# collatz_box.net
KiCad netlist of a schematic drawn in EAGLE
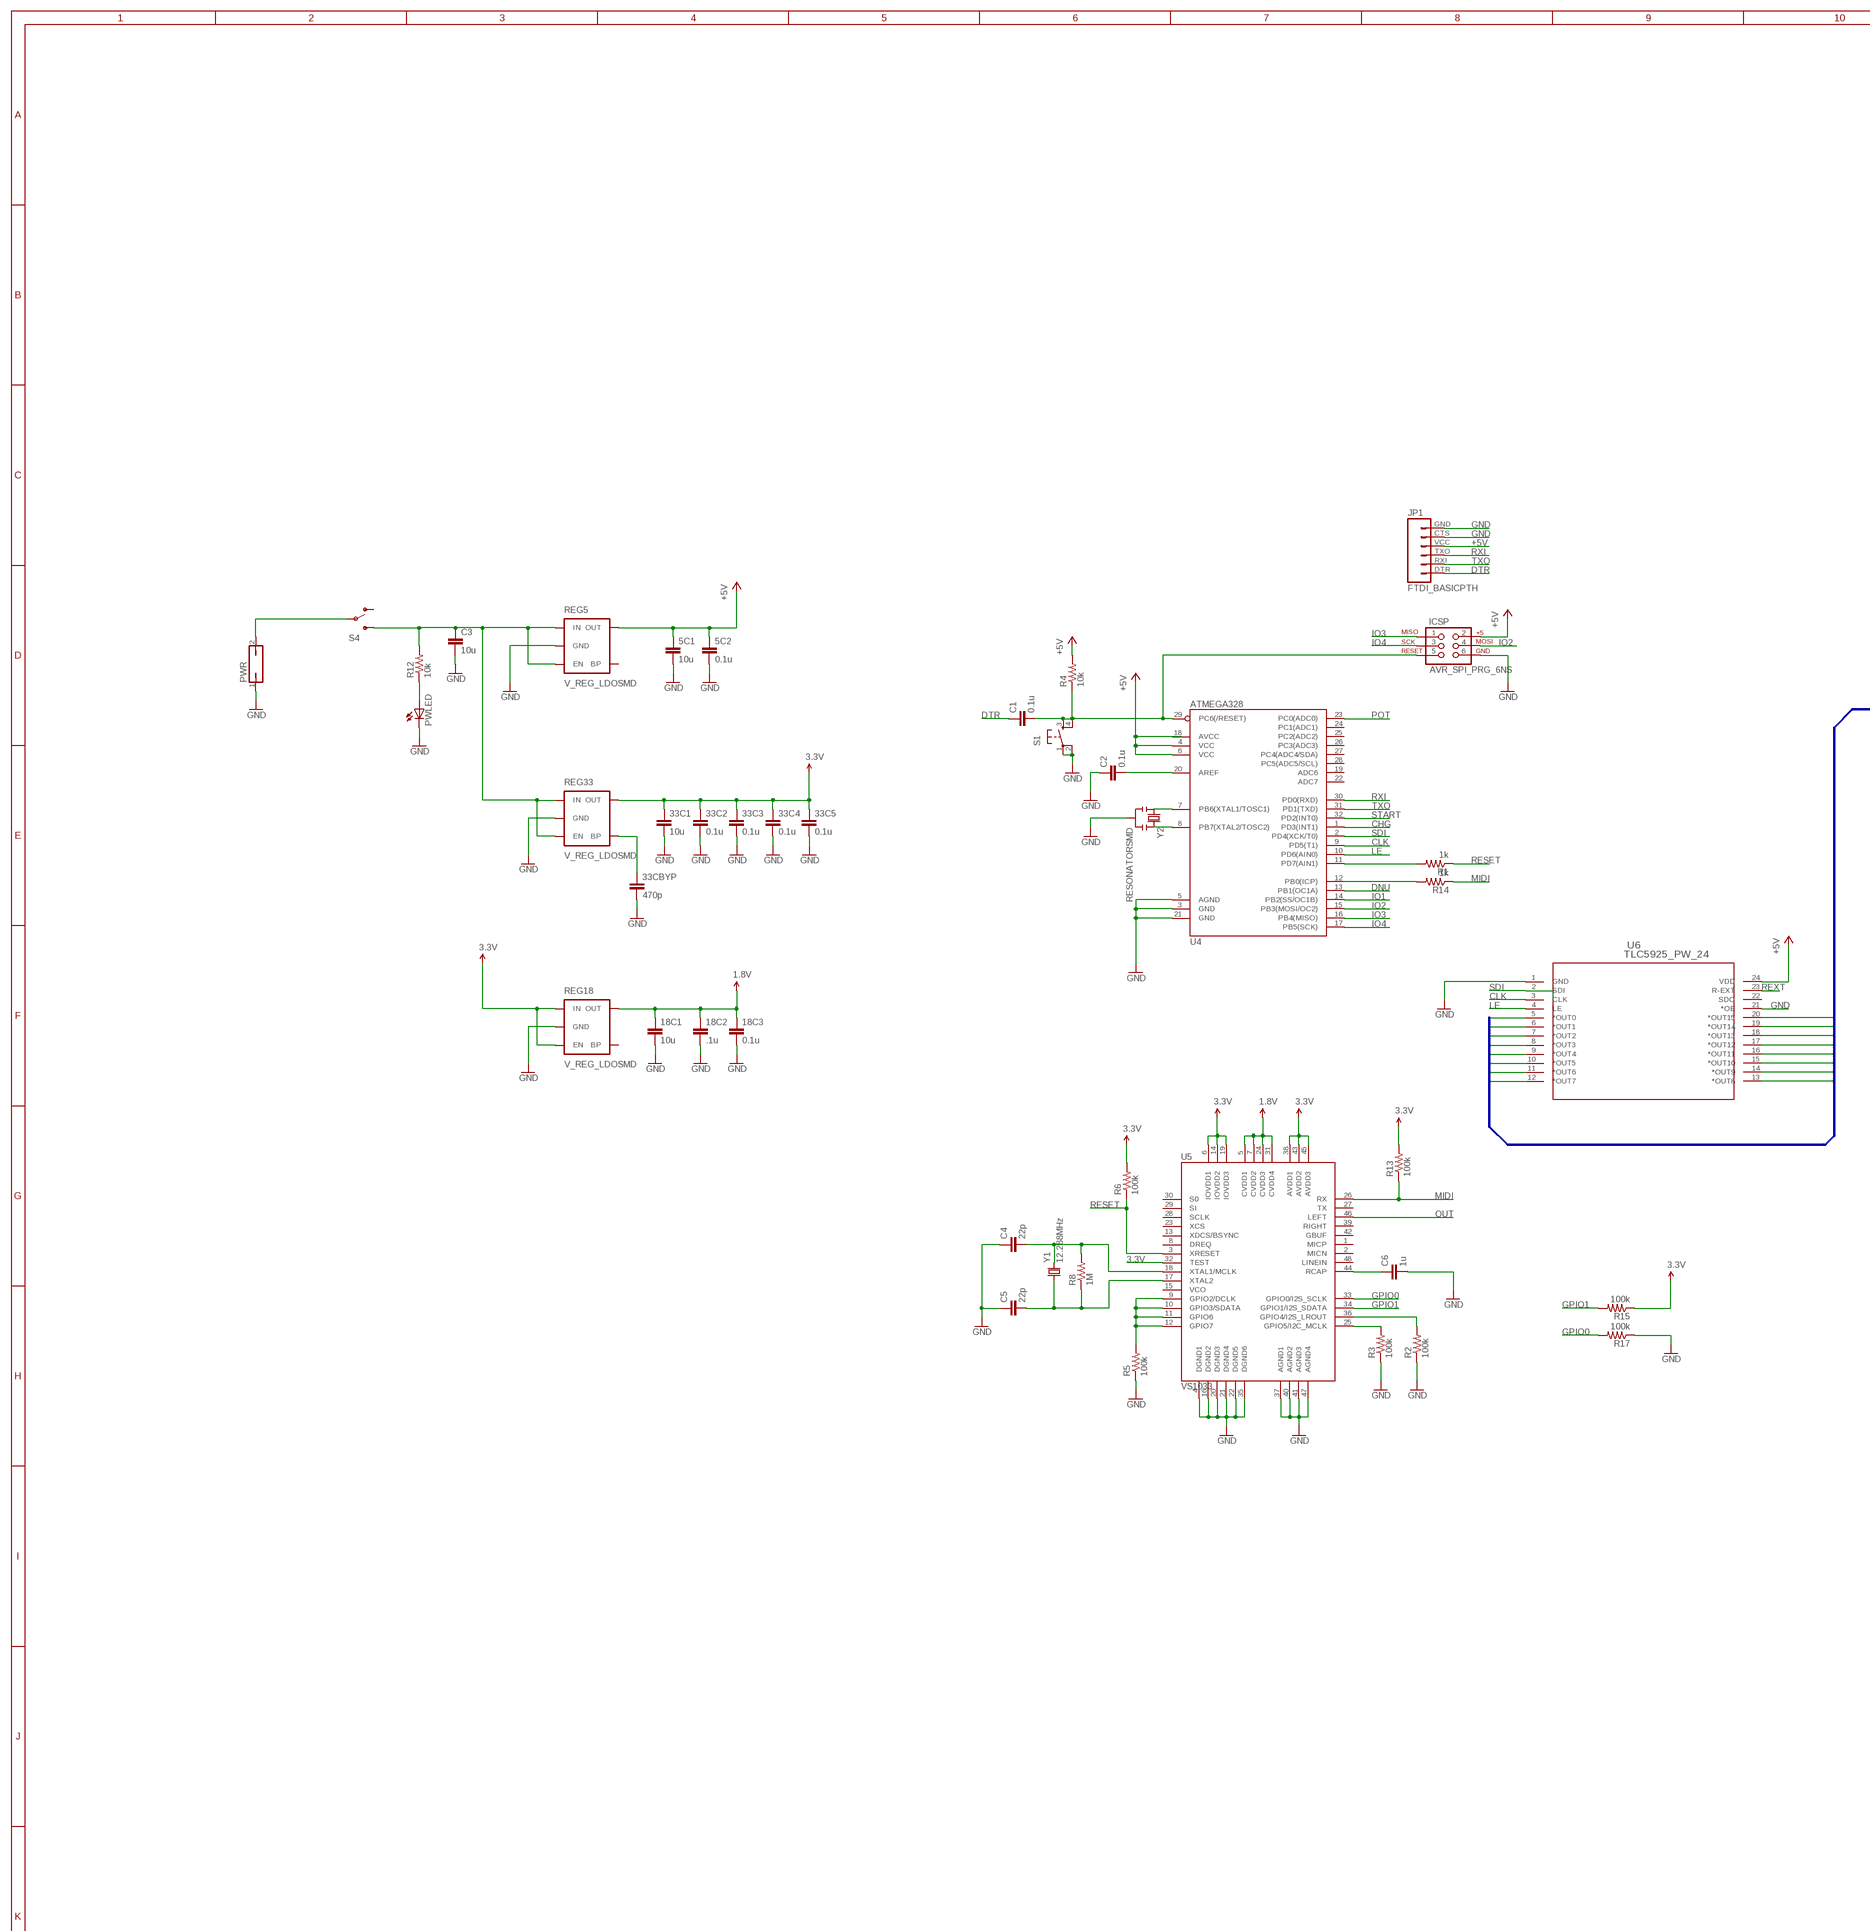
[diagram p0: schematic, sheet 1, part 1 of 3]
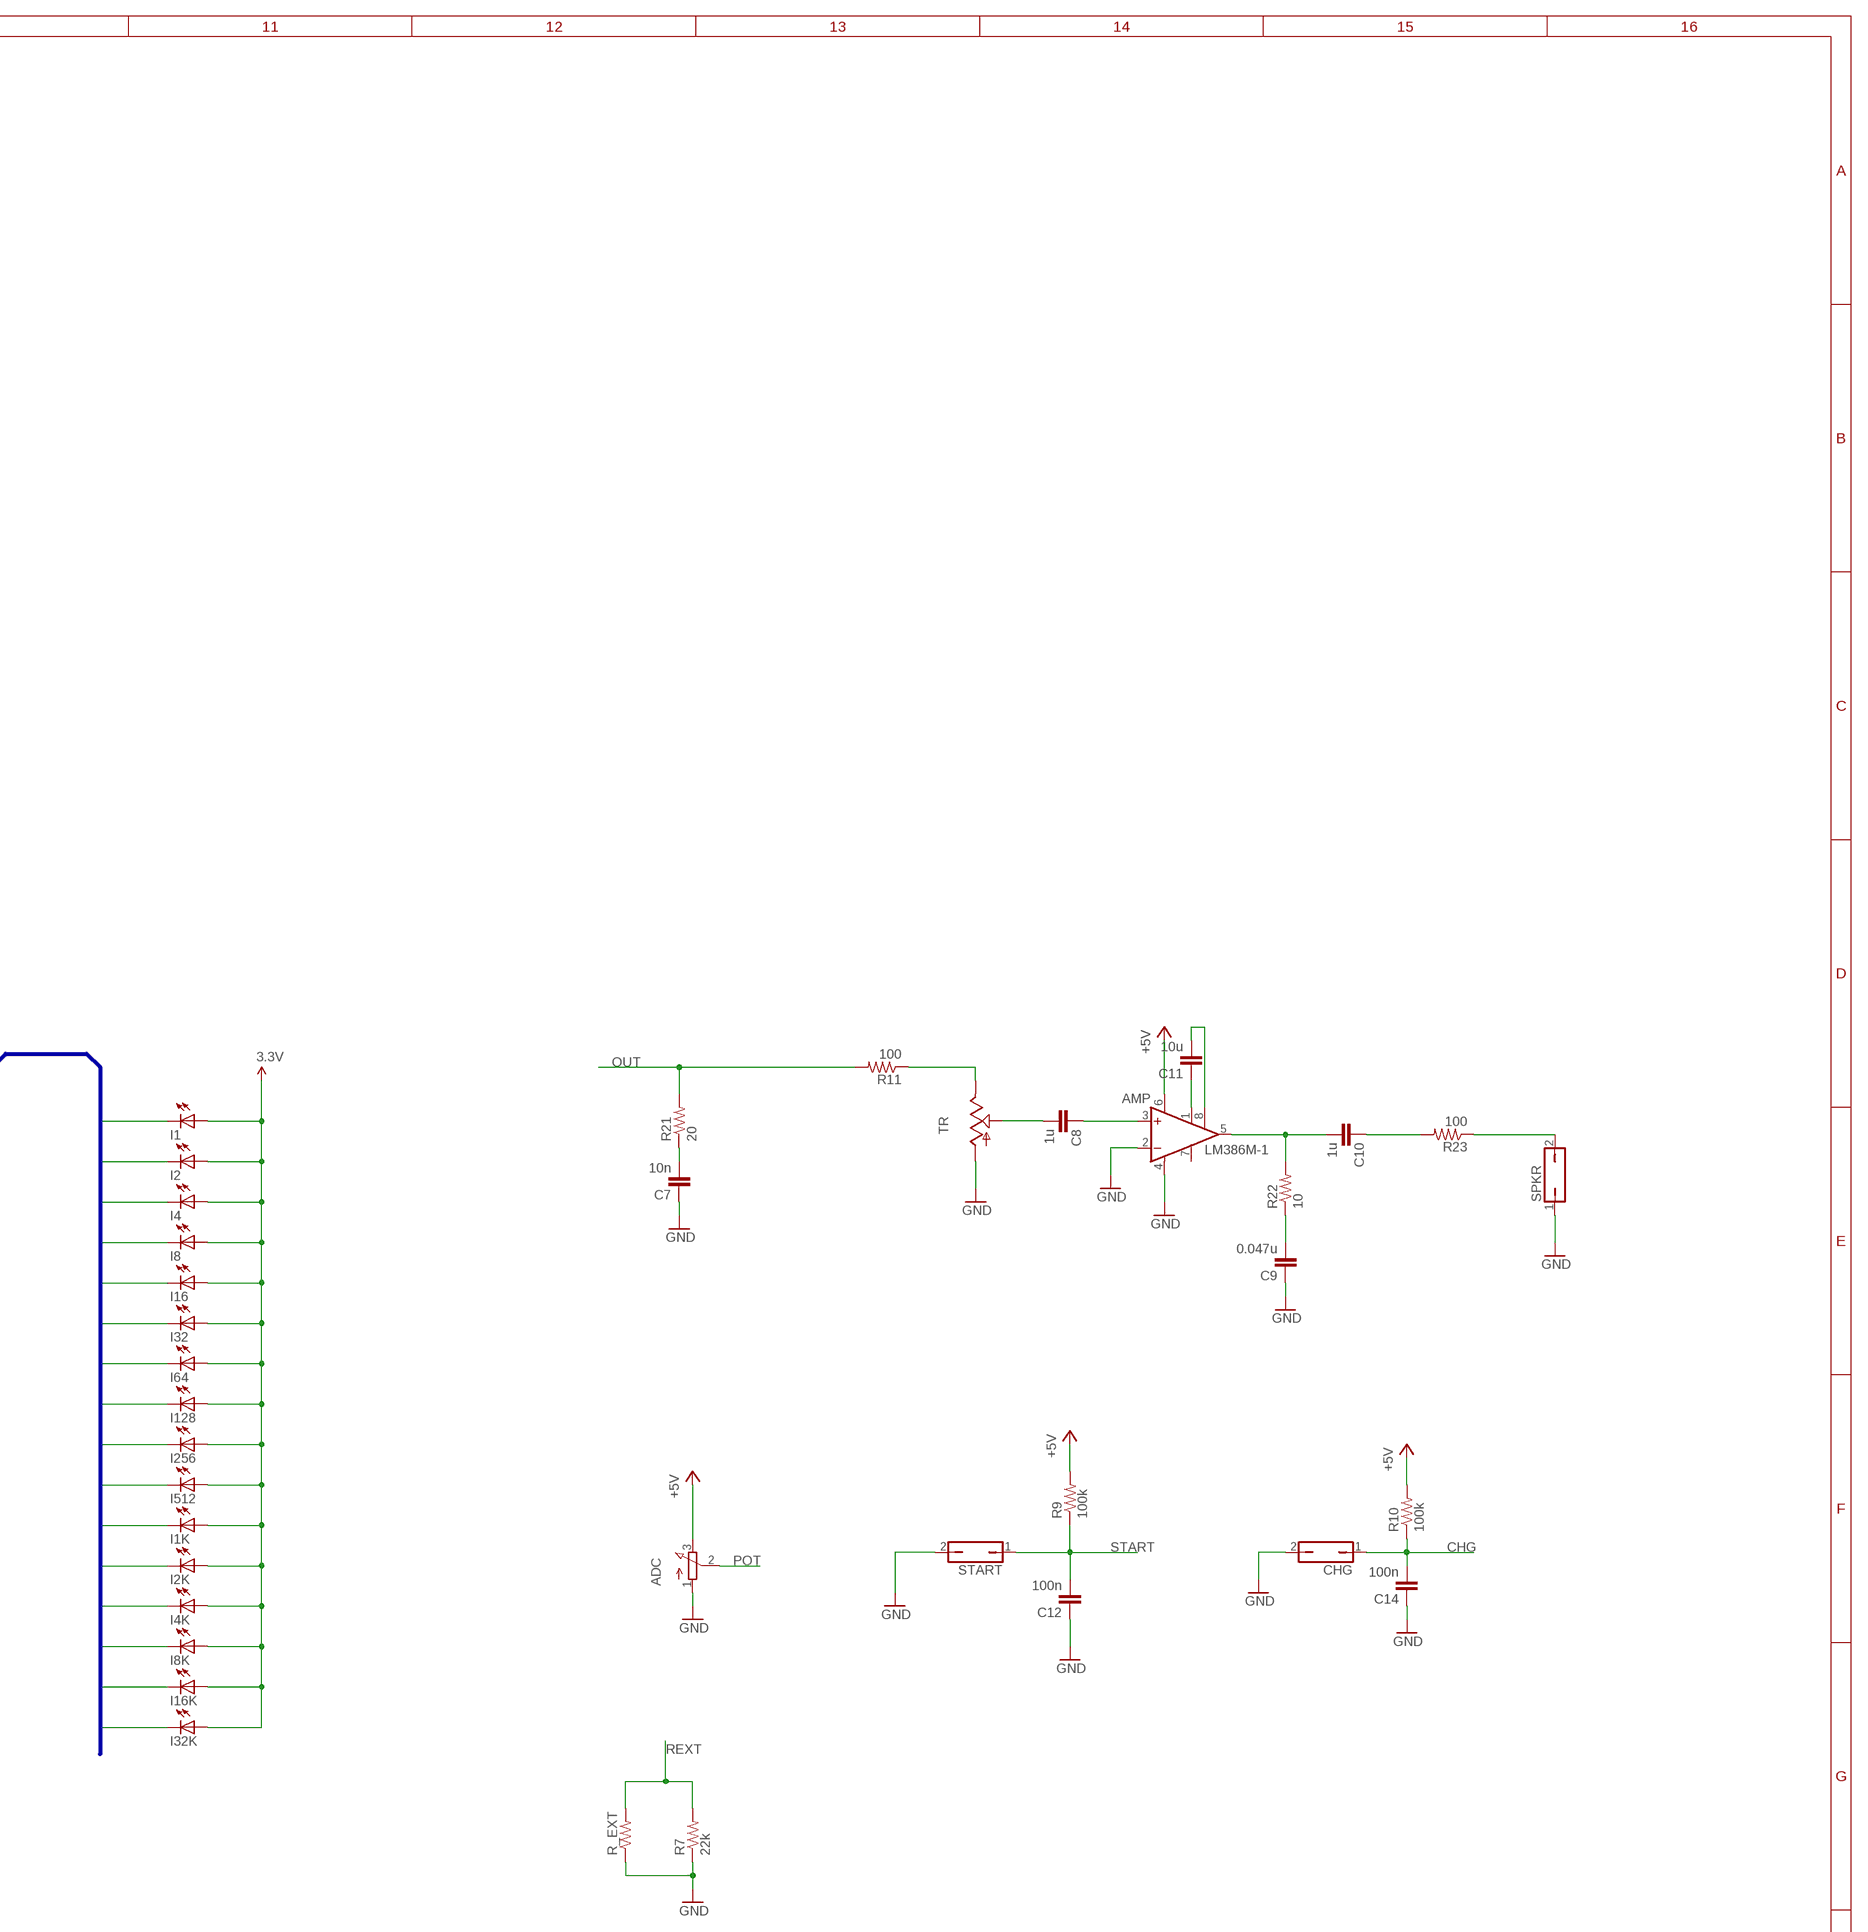
[diagram p1: schematic, sheet 1, part 2 of 3]
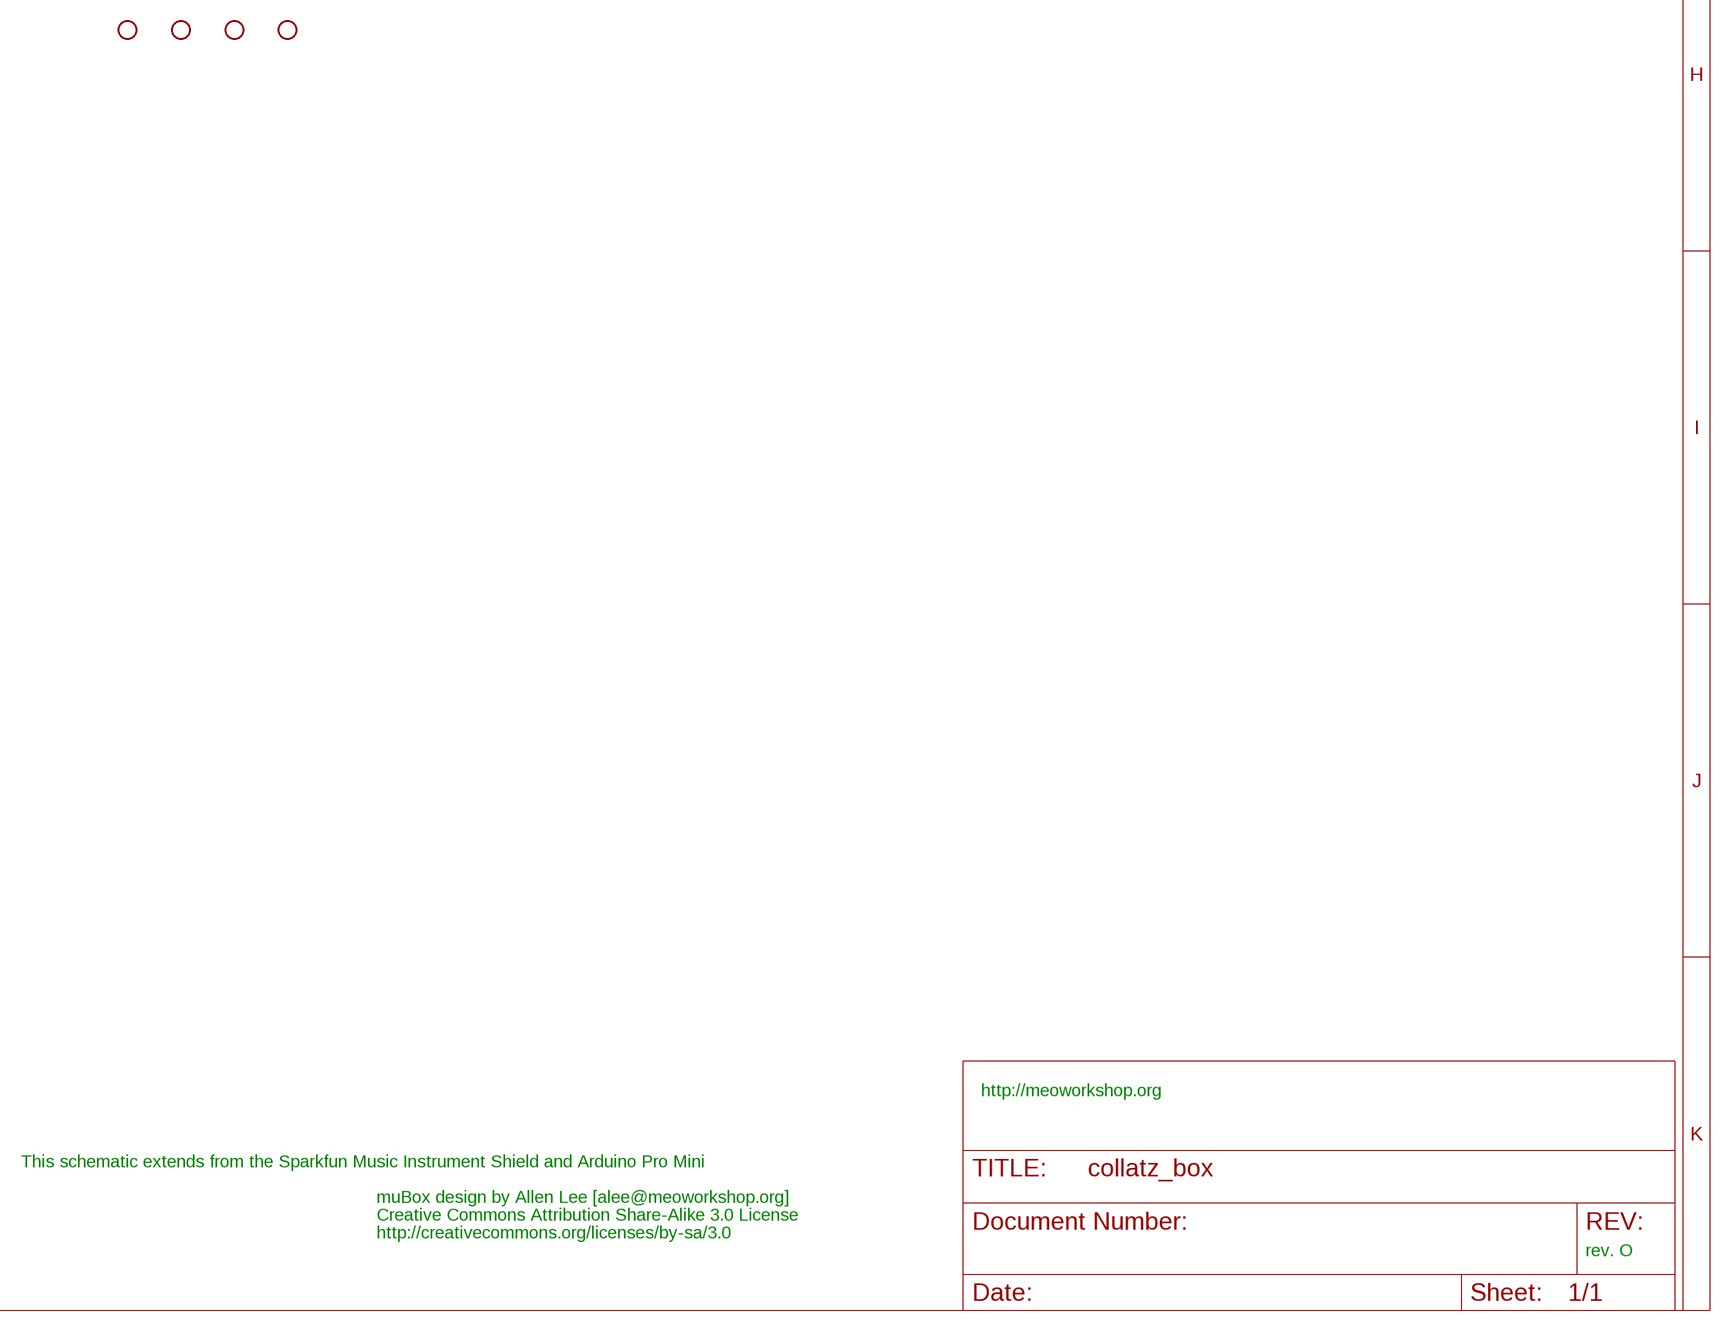
[diagram p2: schematic, sheet 1, part 3 of 3]

(export (version "E")
  (design (tool "Eeschema 10.0.6"))
  (components
    (comp (ref "5C1")
      (value "10u")
      (footprint "eagle-import:1206")
      (libsource (lib "eagle-import") (part "SparkFun-Passives_CAP1206"))
    )
    (comp (ref "5C2")
      (value "0.1u")
      (footprint "eagle-import:0805")
      (libsource (lib "eagle-import") (part "CAP0805"))
    )
    (comp (ref "18C1")
      (value "10u")
      (footprint "eagle-import:1206")
      (libsource (lib "eagle-import") (part "SparkFun-Passives_CAP1206"))
    )
    (comp (ref "18C2")
      (value ".1u")
      (footprint "eagle-import:0805")
      (libsource (lib "eagle-import") (part "CAP0805"))
    )
    (comp (ref "18C3")
      (value "0.1u")
      (footprint "eagle-import:0805")
      (libsource (lib "eagle-import") (part "CAP0805"))
    )
    (comp (ref "33C1")
      (value "10u")
      (footprint "eagle-import:1206")
      (libsource (lib "eagle-import") (part "SparkFun-Passives_CAP1206"))
    )
    (comp (ref "33C2")
      (value "0.1u")
      (footprint "eagle-import:0805")
      (libsource (lib "eagle-import") (part "CAP0805"))
    )
    (comp (ref "33C3")
      (value "0.1u")
      (footprint "eagle-import:0805")
      (libsource (lib "eagle-import") (part "CAP0805"))
    )
    (comp (ref "33C4")
      (value "0.1u")
      (footprint "eagle-import:0805")
      (libsource (lib "eagle-import") (part "CAP0805"))
    )
    (comp (ref "33C5")
      (value "0.1u")
      (footprint "eagle-import:0805")
      (libsource (lib "eagle-import") (part "CAP0805"))
    )
    (comp (ref "33CBYP")
      (value "470p")
      (footprint "eagle-import:0805")
      (libsource (lib "eagle-import") (part "CAP0805"))
    )
    (comp (ref "ADC")
      (value "3RP/1610N")
      (footprint "eagle-import:3RP_1610N")
      (libsource (lib "eagle-import") (part "3RP/1610N"))
    )
    (comp (ref "AMP")
      (value "LM386M-1")
      (footprint "eagle-import:SO08")
      (libsource (lib "eagle-import") (part "LM386?-M1"))
    )
    (comp (ref "C1")
      (value "0.1u")
      (footprint "eagle-import:0805")
      (libsource (lib "eagle-import") (part "CAP0805"))
    )
    (comp (ref "C2")
      (value "0.1u")
      (footprint "eagle-import:0805")
      (libsource (lib "eagle-import") (part "CAP0805"))
    )
    (comp (ref "C3")
      (value "10u")
      (footprint "eagle-import:1206")
      (libsource (lib "eagle-import") (part "SparkFun-Passives_CAP1206"))
    )
    (comp (ref "C4")
      (value "22p")
      (footprint "eagle-import:0805")
      (libsource (lib "eagle-import") (part "CAP0805"))
    )
    (comp (ref "C5")
      (value "22p")
      (footprint "eagle-import:0805")
      (libsource (lib "eagle-import") (part "CAP0805"))
    )
    (comp (ref "C6")
      (value "1u")
      (footprint "eagle-import:0805")
      (libsource (lib "eagle-import") (part "CAP0805"))
    )
    (comp (ref "C7")
      (value "10n")
      (footprint "eagle-import:0805")
      (libsource (lib "eagle-import") (part "CAP0805"))
    )
    (comp (ref "C8")
      (value "1u")
      (footprint "eagle-import:0805")
      (libsource (lib "eagle-import") (part "CAP0805"))
    )
    (comp (ref "C9")
      (value "0.047u")
      (footprint "eagle-import:0805")
      (libsource (lib "eagle-import") (part "CAP0805"))
    )
    (comp (ref "C10")
      (value "1u")
      (footprint "eagle-import:0805")
      (libsource (lib "eagle-import") (part "CAP0805"))
    )
    (comp (ref "C11")
      (value "10u")
      (footprint "eagle-import:0805")
      (libsource (lib "eagle-import") (part "CAP0805"))
    )
    (comp (ref "C12")
      (value "100n")
      (footprint "eagle-import:0805")
      (libsource (lib "eagle-import") (part "CAP0805"))
    )
    (comp (ref "C14")
      (value "100n")
      (footprint "eagle-import:0805")
      (libsource (lib "eagle-import") (part "CAP0805"))
    )
    (comp (ref "CHG")
      (value "JP1Q")
      (footprint "eagle-import:JP1")
      (libsource (lib "eagle-import") (part "JP1Q"))
    )
    (comp (ref "I1")
      (value "LEDCHIPLED_1206")
      (footprint "eagle-import:CHIPLED_1206")
      (libsource (lib "eagle-import") (part "LEDCHIPLED_1206"))
    )
    (comp (ref "I1K")
      (value "LEDCHIPLED_1206")
      (footprint "eagle-import:CHIPLED_1206")
      (libsource (lib "eagle-import") (part "LEDCHIPLED_1206"))
    )
    (comp (ref "I2")
      (value "LEDCHIPLED_1206")
      (footprint "eagle-import:CHIPLED_1206")
      (libsource (lib "eagle-import") (part "LEDCHIPLED_1206"))
    )
    (comp (ref "I2K")
      (value "LEDCHIPLED_1206")
      (footprint "eagle-import:CHIPLED_1206")
      (libsource (lib "eagle-import") (part "LEDCHIPLED_1206"))
    )
    (comp (ref "I4")
      (value "LEDCHIPLED_1206")
      (footprint "eagle-import:CHIPLED_1206")
      (libsource (lib "eagle-import") (part "LEDCHIPLED_1206"))
    )
    (comp (ref "I4K")
      (value "LEDCHIPLED_1206")
      (footprint "eagle-import:CHIPLED_1206")
      (libsource (lib "eagle-import") (part "LEDCHIPLED_1206"))
    )
    (comp (ref "I8")
      (value "LEDCHIPLED_1206")
      (footprint "eagle-import:CHIPLED_1206")
      (libsource (lib "eagle-import") (part "LEDCHIPLED_1206"))
    )
    (comp (ref "I8K")
      (value "LEDCHIPLED_1206")
      (footprint "eagle-import:CHIPLED_1206")
      (libsource (lib "eagle-import") (part "LEDCHIPLED_1206"))
    )
    (comp (ref "I16")
      (value "LEDCHIPLED_1206")
      (footprint "eagle-import:CHIPLED_1206")
      (libsource (lib "eagle-import") (part "LEDCHIPLED_1206"))
    )
    (comp (ref "I16K")
      (value "LEDCHIPLED_1206")
      (footprint "eagle-import:CHIPLED_1206")
      (libsource (lib "eagle-import") (part "LEDCHIPLED_1206"))
    )
    (comp (ref "I32")
      (value "LEDCHIPLED_1206")
      (footprint "eagle-import:CHIPLED_1206")
      (libsource (lib "eagle-import") (part "LEDCHIPLED_1206"))
    )
    (comp (ref "I32K")
      (value "LEDCHIPLED_1206")
      (footprint "eagle-import:CHIPLED_1206")
      (libsource (lib "eagle-import") (part "LEDCHIPLED_1206"))
    )
    (comp (ref "I64")
      (value "LEDCHIPLED_1206")
      (footprint "eagle-import:CHIPLED_1206")
      (libsource (lib "eagle-import") (part "LEDCHIPLED_1206"))
    )
    (comp (ref "I128")
      (value "LEDCHIPLED_1206")
      (footprint "eagle-import:CHIPLED_1206")
      (libsource (lib "eagle-import") (part "LEDCHIPLED_1206"))
    )
    (comp (ref "I256")
      (value "LEDCHIPLED_1206")
      (footprint "eagle-import:CHIPLED_1206")
      (libsource (lib "eagle-import") (part "LEDCHIPLED_1206"))
    )
    (comp (ref "I512")
      (value "LEDCHIPLED_1206")
      (footprint "eagle-import:CHIPLED_1206")
      (libsource (lib "eagle-import") (part "LEDCHIPLED_1206"))
    )
    (comp (ref "ICSP")
      (value "AVR_SPI_PRG_6NS")
      (footprint "eagle-import:2X3-NS")
      (libsource (lib "eagle-import") (part "AVR_SPI_PRG_6NS"))
    )
    (comp (ref "JP1")
      (value "FTDI_BASICPTH")
      (footprint "eagle-import:FTDI_BASIC")
      (libsource (lib "eagle-import") (part "FTDI_BASICPTH"))
    )
    (comp (ref "JP2")
      (value "STAND-OFF")
      (footprint "eagle-import:STAND-OFF")
      (libsource (lib "eagle-import") (part "STAND-OFF"))
    )
    (comp (ref "JP3")
      (value "STAND-OFF")
      (footprint "eagle-import:STAND-OFF")
      (libsource (lib "eagle-import") (part "STAND-OFF"))
    )
    (comp (ref "JP4")
      (value "STAND-OFF")
      (footprint "eagle-import:STAND-OFF")
      (libsource (lib "eagle-import") (part "STAND-OFF"))
    )
    (comp (ref "JP5")
      (value "STAND-OFF")
      (footprint "eagle-import:STAND-OFF")
      (libsource (lib "eagle-import") (part "STAND-OFF"))
    )
    (comp (ref "PWLED")
      (value "LEDCHIPLED_1206")
      (footprint "eagle-import:CHIPLED_1206")
      (libsource (lib "eagle-import") (part "LEDCHIPLED_1206"))
    )
    (comp (ref "PWR")
      (value "JP1Q")
      (footprint "eagle-import:JP1")
      (libsource (lib "eagle-import") (part "JP1Q"))
    )
    (comp (ref "R1")
      (value "1k")
      (footprint "eagle-import:0805")
      (libsource (lib "eagle-import") (part "RESISTOR0805-RES"))
    )
    (comp (ref "R2")
      (value "100k")
      (footprint "eagle-import:0805")
      (libsource (lib "eagle-import") (part "RESISTOR0805-RES"))
    )
    (comp (ref "R3")
      (value "100k")
      (footprint "eagle-import:0805")
      (libsource (lib "eagle-import") (part "RESISTOR0805-RES"))
    )
    (comp (ref "R4")
      (value "10k")
      (footprint "eagle-import:0805")
      (libsource (lib "eagle-import") (part "RESISTOR0805-RES"))
    )
    (comp (ref "R5")
      (value "100k")
      (footprint "eagle-import:0805")
      (libsource (lib "eagle-import") (part "RESISTOR0805-RES"))
    )
    (comp (ref "R6")
      (value "100k")
      (footprint "eagle-import:0805")
      (libsource (lib "eagle-import") (part "RESISTOR0805-RES"))
    )
    (comp (ref "R7")
      (value "22k")
      (footprint "eagle-import:0805")
      (libsource (lib "eagle-import") (part "RESISTOR0805-RES"))
    )
    (comp (ref "R8")
      (value "1M")
      (footprint "eagle-import:0805")
      (libsource (lib "eagle-import") (part "RESISTOR0805-RES"))
    )
    (comp (ref "R9")
      (value "100k")
      (footprint "eagle-import:0805")
      (libsource (lib "eagle-import") (part "RESISTOR0805-RES"))
    )
    (comp (ref "R10")
      (value "100k")
      (footprint "eagle-import:0805")
      (libsource (lib "eagle-import") (part "RESISTOR0805-RES"))
    )
    (comp (ref "R11")
      (value "100")
      (footprint "eagle-import:0805")
      (libsource (lib "eagle-import") (part "RESISTOR0805-RES"))
    )
    (comp (ref "R12")
      (value "10k")
      (footprint "eagle-import:0805")
      (libsource (lib "eagle-import") (part "RESISTOR0805-RES"))
    )
    (comp (ref "R13")
      (value "100k")
      (footprint "eagle-import:0805")
      (libsource (lib "eagle-import") (part "RESISTOR0805-RES"))
    )
    (comp (ref "R14")
      (value "1k")
      (footprint "eagle-import:0805")
      (libsource (lib "eagle-import") (part "RESISTOR0805-RES"))
    )
    (comp (ref "R15")
      (value "100k")
      (footprint "eagle-import:0805")
      (libsource (lib "eagle-import") (part "RESISTOR0805-RES"))
    )
    (comp (ref "R17")
      (value "100k")
      (footprint "eagle-import:0805")
      (libsource (lib "eagle-import") (part "RESISTOR0805-RES"))
    )
    (comp (ref "R21")
      (value "20")
      (footprint "eagle-import:0805")
      (libsource (lib "eagle-import") (part "RESISTOR0805-RES"))
    )
    (comp (ref "R22")
      (value "10")
      (footprint "eagle-import:0805")
      (libsource (lib "eagle-import") (part "RESISTOR0805-RES"))
    )
    (comp (ref "R23")
      (value "100")
      (footprint "eagle-import:0805")
      (libsource (lib "eagle-import") (part "RESISTOR0805-RES"))
    )
    (comp (ref "REG5")
      (value "V_REG_LDOSMD")
      (footprint "eagle-import:SOT23-5")
      (libsource (lib "eagle-import") (part "V_REG_LDOSMD"))
    )
    (comp (ref "REG18")
      (value "V_REG_LDOSMD")
      (footprint "eagle-import:SOT23-5")
      (libsource (lib "eagle-import") (part "V_REG_LDOSMD"))
    )
    (comp (ref "REG33")
      (value "V_REG_LDOSMD")
      (footprint "eagle-import:SOT23-5")
      (libsource (lib "eagle-import") (part "V_REG_LDOSMD"))
    )
    (comp (ref "R_EXT")
      (value "RESISTORPTH-1/4W")
      (footprint "eagle-import:AXIAL-0.4")
      (libsource (lib "eagle-import") (part "SparkFun-Resistors_RESISTORPTH-1/4W"))
    )
    (comp (ref "S1")
      (value "TAC_SWITCHSMD")
      (footprint "eagle-import:TACTILE_SWITCH_SMD")
      (libsource (lib "eagle-import") (part "TAC_SWITCHSMD"))
    )
    (comp (ref "S4")
      (value "SWITCH-SPDTPTH")
      (footprint "eagle-import:SWITCH-SPDT")
      (libsource (lib "eagle-import") (part "SWITCH-SPDTPTH"))
    )
    (comp (ref "SPKR")
      (value "JP1Q")
      (footprint "eagle-import:JP1")
      (libsource (lib "eagle-import") (part "JP1Q"))
    )
    (comp (ref "START")
      (value "JP1Q")
      (footprint "eagle-import:JP1")
      (libsource (lib "eagle-import") (part "JP1Q"))
    )
    (comp (ref "TR")
      (value "TRIM_US-3223W")
      (footprint "eagle-import:3223W")
      (libsource (lib "eagle-import") (part "TRIM_US-3223W"))
    )
    (comp (ref "U4")
      (value "ATMEGA328")
      (footprint "eagle-import:TQFP32-08")
      (libsource (lib "eagle-import") (part "ATMEGA168"))
    )
    (comp (ref "U5")
      (value "VS1033")
      (footprint "eagle-import:LQFP-48")
      (libsource (lib "eagle-import") (part "VS1033"))
    )
    (comp (ref "U6")
      (value "TLC5925_PW_24")
      (footprint "eagle-import:PW24")
      (fields
        (field (name "GENERIC_PART_NUMBER") "TLC5925")
        (field (name "MANUFACTURER") "Texas Instruments")
        (field (name "MANUFACTURER_PART_NUMBER") "tlc5925_pw_24")
      )
      (libsource (lib "eagle-import") (part "TLC5925_PW_24"))
    )
    (comp (ref "Y1")
      (value "12.288MHz")
      (footprint "eagle-import:CRYSTAL-SMD-5X3")
      (libsource (lib "eagle-import") (part "CRYSTAL5X3"))
    )
    (comp (ref "Y2")
      (value "RESONATORSMD")
      (footprint "eagle-import:RESONATOR-SMD")
      (libsource (lib "eagle-import") (part "RESONATORSMD"))
    )
  )
  (nets
    (net (code "1") (name "+5V") (class "Default")
      (node (ref "5C1") (pin "1") (pinfunction "1_1") (pintype "passive"))
      (node (ref "5C2") (pin "1") (pinfunction "1_1") (pintype "passive"))
      (node (ref "ADC") (pin "3") (pinfunction "E_3") (pintype "passive"))
      (node (ref "AMP") (pin "6") (pinfunction "VS_6") (pintype "power_in"))
      (node (ref "ICSP") (pin "2") (pinfunction "2_2") (pintype "passive"))
      (node (ref "JP1") (pin "VCC") (pinfunction "4_VCC") (pintype "passive"))
      (node (ref "R10") (pin "2") (pinfunction "2_2") (pintype "passive"))
      (node (ref "R4") (pin "2") (pinfunction "2_2") (pintype "passive"))
      (node (ref "R9") (pin "2") (pinfunction "2_2") (pintype "passive"))
      (node (ref "REG5") (pin "5") (pinfunction "OUT_5") (pintype "passive"))
      (node (ref "U4") (pin "4") (pinfunction "VCC_4") (pintype "bidirectional"))
      (node (ref "U4") (pin "6") (pinfunction "VCC_6") (pintype "bidirectional"))
      (node (ref "U6") (pin "24") (pinfunction "VDD_24") (pintype "power_in"))
    )
    (net (code "2") (name "/CHG") (class "Default")
      (node (ref "C14") (pin "2") (pinfunction "2_2") (pintype "passive"))
      (node (ref "CHG") (pin "1") (pinfunction "1_1") (pintype "passive"))
      (node (ref "R10") (pin "1") (pinfunction "1_1") (pintype "passive"))
      (node (ref "U4") (pin "1") (pinfunction "PD3(INT1)_1") (pintype "bidirectional"))
    )
    (net (code "3") (name "/CLK") (class "Default")
      (node (ref "U4") (pin "9") (pinfunction "PD5(T1)_9") (pintype "bidirectional"))
      (node (ref "U6") (pin "3") (pinfunction "CLK_3") (pintype "input"))
    )
    (net (code "4") (name "/DNU") (class "Default")
      (node (ref "U4") (pin "13") (pinfunction "PB1(OC1A)_13") (pintype "bidirectional"))
    )
    (net (code "5") (name "/DTR") (class "Default")
      (node (ref "C1") (pin "1") (pinfunction "1_1") (pintype "passive"))
      (node (ref "C1") (pin "2") (pinfunction "2_2") (pintype "passive"))
      (node (ref "ICSP") (pin "5") (pinfunction "5_5") (pintype "passive"))
      (node (ref "JP1") (pin "DTR") (pinfunction "1_DTR") (pintype "passive"))
      (node (ref "R4") (pin "1") (pinfunction "1_1") (pintype "passive"))
      (node (ref "S1") (pin "3") (pinfunction "3_3") (pintype "passive"))
      (node (ref "S1") (pin "4") (pinfunction "4_4") (pintype "passive"))
      (node (ref "U4") (pin "29") (pinfunction "PC6(/RESET)_29") (pintype "bidirectional"))
    )
    (net (code "6") (name "/GPIO0") (class "Default")
      (node (ref "R17") (pin "2") (pinfunction "2_2") (pintype "passive"))
      (node (ref "U5") (pin "33") (pinfunction "GPIO0/I2S_SCLK_33") (pintype "bidirectional"))
    )
    (net (code "7") (name "/GPIO1") (class "Default")
      (node (ref "R15") (pin "2") (pinfunction "2_2") (pintype "passive"))
      (node (ref "U5") (pin "34") (pinfunction "GPIO1/I2S_SDATA_34") (pintype "bidirectional"))
    )
    (net (code "8") (name "/IO1") (class "Default")
      (node (ref "U4") (pin "14") (pinfunction "PB2(SS/OC1B)_14") (pintype "bidirectional"))
    )
    (net (code "9") (name "/IO2") (class "Default")
      (node (ref "ICSP") (pin "4") (pinfunction "4_4") (pintype "passive"))
      (node (ref "U4") (pin "15") (pinfunction "PB3(MOSI/OC2)_15") (pintype "bidirectional"))
    )
    (net (code "10") (name "/IO3") (class "Default")
      (node (ref "ICSP") (pin "1") (pinfunction "1_1") (pintype "passive"))
      (node (ref "U4") (pin "16") (pinfunction "PB4(MISO)_16") (pintype "bidirectional"))
    )
    (net (code "11") (name "/IO4") (class "Default")
      (node (ref "ICSP") (pin "3") (pinfunction "3_3") (pintype "passive"))
      (node (ref "U4") (pin "17") (pinfunction "PB5(SCK)_17") (pintype "bidirectional"))
    )
    (net (code "12") (name "/LE") (class "Default")
      (node (ref "U4") (pin "10") (pinfunction "PD6(AIN0)_10") (pintype "bidirectional"))
      (node (ref "U6") (pin "4") (pinfunction "LE_4") (pintype "input"))
    )
    (net (code "13") (name "/MIDI") (class "Default")
      (node (ref "R13") (pin "1") (pinfunction "1_1") (pintype "passive"))
      (node (ref "R14") (pin "1") (pinfunction "1_1") (pintype "passive"))
      (node (ref "U5") (pin "26") (pinfunction "RX_26") (pintype "bidirectional"))
    )
    (net (code "14") (name "/OUT") (class "Default")
      (node (ref "R11") (pin "2") (pinfunction "2_2") (pintype "passive"))
      (node (ref "R21") (pin "2") (pinfunction "2_2") (pintype "passive"))
      (node (ref "U5") (pin "46") (pinfunction "LEFT_46") (pintype "bidirectional"))
    )
    (net (code "15") (name "/OUT0") (class "Default")
      (node (ref "I1") (pin "C") (pinfunction "C_C") (pintype "passive"))
      (node (ref "U6") (pin "5") (pinfunction "*OUT0_5") (pintype "output"))
    )
    (net (code "16") (name "/OUT1") (class "Default")
      (node (ref "I2") (pin "C") (pinfunction "C_C") (pintype "passive"))
      (node (ref "U6") (pin "6") (pinfunction "*OUT1_6") (pintype "output"))
    )
    (net (code "17") (name "/OUT2") (class "Default")
      (node (ref "I4") (pin "C") (pinfunction "C_C") (pintype "passive"))
      (node (ref "U6") (pin "7") (pinfunction "*OUT2_7") (pintype "output"))
    )
    (net (code "18") (name "/OUT3") (class "Default")
      (node (ref "I8") (pin "C") (pinfunction "C_C") (pintype "passive"))
      (node (ref "U6") (pin "8") (pinfunction "*OUT3_8") (pintype "output"))
    )
    (net (code "19") (name "/OUT4") (class "Default")
      (node (ref "I16") (pin "C") (pinfunction "C_C") (pintype "passive"))
      (node (ref "U6") (pin "9") (pinfunction "*OUT4_9") (pintype "output"))
    )
    (net (code "20") (name "/OUT5") (class "Default")
      (node (ref "I32") (pin "C") (pinfunction "C_C") (pintype "passive"))
      (node (ref "U6") (pin "10") (pinfunction "*OUT5_10") (pintype "output"))
    )
    (net (code "21") (name "/OUT6") (class "Default")
      (node (ref "I64") (pin "C") (pinfunction "C_C") (pintype "passive"))
      (node (ref "U6") (pin "11") (pinfunction "*OUT6_11") (pintype "output"))
    )
    (net (code "22") (name "/OUT7") (class "Default")
      (node (ref "I128") (pin "C") (pinfunction "C_C") (pintype "passive"))
      (node (ref "U6") (pin "12") (pinfunction "*OUT7_12") (pintype "output"))
    )
    (net (code "23") (name "/OUT8") (class "Default")
      (node (ref "I256") (pin "C") (pinfunction "C_C") (pintype "passive"))
      (node (ref "U6") (pin "13") (pinfunction "*OUT8_13") (pintype "output"))
    )
    (net (code "24") (name "/OUT9") (class "Default")
      (node (ref "I512") (pin "C") (pinfunction "C_C") (pintype "passive"))
      (node (ref "U6") (pin "14") (pinfunction "*OUT9_14") (pintype "output"))
    )
    (net (code "25") (name "/OUT10") (class "Default")
      (node (ref "I1K") (pin "C") (pinfunction "C_C") (pintype "passive"))
      (node (ref "U6") (pin "15") (pinfunction "*OUT10_15") (pintype "output"))
    )
    (net (code "26") (name "/OUT11") (class "Default")
      (node (ref "I2K") (pin "C") (pinfunction "C_C") (pintype "passive"))
      (node (ref "U6") (pin "16") (pinfunction "*OUT11_16") (pintype "output"))
    )
    (net (code "27") (name "/OUT12") (class "Default")
      (node (ref "I4K") (pin "C") (pinfunction "C_C") (pintype "passive"))
      (node (ref "U6") (pin "17") (pinfunction "*OUT12_17") (pintype "output"))
    )
    (net (code "28") (name "/OUT13") (class "Default")
      (node (ref "I8K") (pin "C") (pinfunction "C_C") (pintype "passive"))
      (node (ref "U6") (pin "18") (pinfunction "*OUT13_18") (pintype "output"))
    )
    (net (code "29") (name "/OUT14") (class "Default")
      (node (ref "I16K") (pin "C") (pinfunction "C_C") (pintype "passive"))
      (node (ref "U6") (pin "19") (pinfunction "*OUT14_19") (pintype "output"))
    )
    (net (code "30") (name "/OUT15") (class "Default")
      (node (ref "I32K") (pin "C") (pinfunction "C_C") (pintype "passive"))
      (node (ref "U6") (pin "20") (pinfunction "*OUT15_20") (pintype "output"))
    )
    (net (code "31") (name "/POT") (class "Default")
      (node (ref "ADC") (pin "2") (pinfunction "S_2") (pintype "passive"))
      (node (ref "U4") (pin "23") (pinfunction "PC0(ADC0)_23") (pintype "bidirectional"))
    )
    (net (code "32") (name "/RESET") (class "Default")
      (node (ref "R1") (pin "1") (pinfunction "1_1") (pintype "passive"))
      (node (ref "R6") (pin "1") (pinfunction "1_1") (pintype "passive"))
      (node (ref "U5") (pin "3") (pinfunction "XRESET_3") (pintype "bidirectional"))
    )
    (net (code "33") (name "/REXT") (class "Default")
      (node (ref "R7") (pin "2") (pinfunction "2_2") (pintype "passive"))
      (node (ref "R_EXT") (pin "P$2") (pinfunction "2_P$2") (pintype "passive"))
      (node (ref "U6") (pin "23") (pinfunction "R-EXT_23") (pintype "input"))
    )
    (net (code "34") (name "/RXI") (class "Default")
      (node (ref "JP1") (pin "TXO") (pinfunction "3_TXO") (pintype "passive"))
      (node (ref "U4") (pin "30") (pinfunction "PD0(RXD)_30") (pintype "bidirectional"))
    )
    (net (code "35") (name "/SDI") (class "Default")
      (node (ref "U4") (pin "2") (pinfunction "PD4(XCK/T0)_2") (pintype "bidirectional"))
      (node (ref "U6") (pin "2") (pinfunction "SDI_2") (pintype "input"))
    )
    (net (code "36") (name "/START") (class "Default")
      (node (ref "C12") (pin "2") (pinfunction "2_2") (pintype "passive"))
      (node (ref "R9") (pin "1") (pinfunction "1_1") (pintype "passive"))
      (node (ref "START") (pin "1") (pinfunction "1_1") (pintype "passive"))
      (node (ref "U4") (pin "32") (pinfunction "PD2(INT0)_32") (pintype "bidirectional"))
    )
    (net (code "37") (name "/TXO") (class "Default")
      (node (ref "JP1") (pin "RXI") (pinfunction "2_RXI") (pintype "passive"))
      (node (ref "U4") (pin "31") (pinfunction "PD1(TXD)_31") (pintype "bidirectional"))
    )
    (net (code "38") (name "1.8V") (class "Default")
      (node (ref "18C1") (pin "1") (pinfunction "1_1") (pintype "passive"))
      (node (ref "18C2") (pin "1") (pinfunction "1_1") (pintype "passive"))
      (node (ref "18C3") (pin "1") (pinfunction "1_1") (pintype "passive"))
      (node (ref "REG18") (pin "5") (pinfunction "OUT_5") (pintype "passive"))
      (node (ref "U5") (pin "24") (pinfunction "CVDD3_24") (pintype "bidirectional"))
      (node (ref "U5") (pin "31") (pinfunction "CVDD4_31") (pintype "bidirectional"))
      (node (ref "U5") (pin "5") (pinfunction "CVDD1_5") (pintype "bidirectional"))
      (node (ref "U5") (pin "7") (pinfunction "CVDD2_7") (pintype "bidirectional"))
    )
    (net (code "39") (name "3.3V") (class "Default")
      (node (ref "33C1") (pin "1") (pinfunction "1_1") (pintype "passive"))
      (node (ref "33C2") (pin "1") (pinfunction "1_1") (pintype "passive"))
      (node (ref "33C3") (pin "1") (pinfunction "1_1") (pintype "passive"))
      (node (ref "33C4") (pin "1") (pinfunction "1_1") (pintype "passive"))
      (node (ref "33C5") (pin "1") (pinfunction "1_1") (pintype "passive"))
      (node (ref "I1") (pin "A") (pinfunction "A_A") (pintype "passive"))
      (node (ref "I128") (pin "A") (pinfunction "A_A") (pintype "passive"))
      (node (ref "I16") (pin "A") (pinfunction "A_A") (pintype "passive"))
      (node (ref "I16K") (pin "A") (pinfunction "A_A") (pintype "passive"))
      (node (ref "I1K") (pin "A") (pinfunction "A_A") (pintype "passive"))
      (node (ref "I2") (pin "A") (pinfunction "A_A") (pintype "passive"))
      (node (ref "I256") (pin "A") (pinfunction "A_A") (pintype "passive"))
      (node (ref "I2K") (pin "A") (pinfunction "A_A") (pintype "passive"))
      (node (ref "I32") (pin "A") (pinfunction "A_A") (pintype "passive"))
      (node (ref "I32K") (pin "A") (pinfunction "A_A") (pintype "passive"))
      (node (ref "I4") (pin "A") (pinfunction "A_A") (pintype "passive"))
      (node (ref "I4K") (pin "A") (pinfunction "A_A") (pintype "passive"))
      (node (ref "I512") (pin "A") (pinfunction "A_A") (pintype "passive"))
      (node (ref "I64") (pin "A") (pinfunction "A_A") (pintype "passive"))
      (node (ref "I8") (pin "A") (pinfunction "A_A") (pintype "passive"))
      (node (ref "I8K") (pin "A") (pinfunction "A_A") (pintype "passive"))
      (node (ref "R13") (pin "2") (pinfunction "2_2") (pintype "passive"))
      (node (ref "R15") (pin "1") (pinfunction "1_1") (pintype "passive"))
      (node (ref "R6") (pin "2") (pinfunction "2_2") (pintype "passive"))
      (node (ref "REG18") (pin "1") (pinfunction "IN_1") (pintype "input"))
      (node (ref "REG18") (pin "3") (pinfunction "EN_3") (pintype "input"))
      (node (ref "REG33") (pin "5") (pinfunction "OUT_5") (pintype "passive"))
      (node (ref "U5") (pin "14") (pinfunction "IOVDD2_14") (pintype "bidirectional"))
      (node (ref "U5") (pin "19") (pinfunction "IOVDD3_19") (pintype "bidirectional"))
      (node (ref "U5") (pin "32") (pinfunction "TEST_32") (pintype "bidirectional"))
      (node (ref "U5") (pin "38") (pinfunction "AVDD1_38") (pintype "bidirectional"))
      (node (ref "U5") (pin "43") (pinfunction "AVDD2_43") (pintype "bidirectional"))
      (node (ref "U5") (pin "45") (pinfunction "AVDD3_45") (pintype "bidirectional"))
      (node (ref "U5") (pin "6") (pinfunction "IOVDD1_6") (pintype "bidirectional"))
    )
    (net (code "40") (name "GND") (class "Default")
      (node (ref "18C1") (pin "2") (pinfunction "2_2") (pintype "passive"))
      (node (ref "18C2") (pin "2") (pinfunction "2_2") (pintype "passive"))
      (node (ref "18C3") (pin "2") (pinfunction "2_2") (pintype "passive"))
      (node (ref "33C1") (pin "2") (pinfunction "2_2") (pintype "passive"))
      (node (ref "33C2") (pin "2") (pinfunction "2_2") (pintype "passive"))
      (node (ref "33C3") (pin "2") (pinfunction "2_2") (pintype "passive"))
      (node (ref "33C4") (pin "2") (pinfunction "2_2") (pintype "passive"))
      (node (ref "33C5") (pin "2") (pinfunction "2_2") (pintype "passive"))
      (node (ref "33CBYP") (pin "2") (pinfunction "2_2") (pintype "passive"))
      (node (ref "5C1") (pin "2") (pinfunction "2_2") (pintype "passive"))
      (node (ref "5C2") (pin "2") (pinfunction "2_2") (pintype "passive"))
      (node (ref "ADC") (pin "1") (pinfunction "A_1") (pintype "passive"))
      (node (ref "AMP") (pin "2") (pinfunction "-IN_2") (pintype "input"))
      (node (ref "AMP") (pin "4") (pinfunction "GND_4") (pintype "power_in"))
      (node (ref "C12") (pin "1") (pinfunction "1_1") (pintype "passive"))
      (node (ref "C14") (pin "1") (pinfunction "1_1") (pintype "passive"))
      (node (ref "C2") (pin "1") (pinfunction "1_1") (pintype "passive"))
      (node (ref "C3") (pin "2") (pinfunction "2_2") (pintype "passive"))
      (node (ref "C4") (pin "1") (pinfunction "1_1") (pintype "passive"))
      (node (ref "C5") (pin "1") (pinfunction "1_1") (pintype "passive"))
      (node (ref "C6") (pin "2") (pinfunction "2_2") (pintype "passive"))
      (node (ref "C7") (pin "1") (pinfunction "1_1") (pintype "passive"))
      (node (ref "C9") (pin "1") (pinfunction "1_1") (pintype "passive"))
      (node (ref "CHG") (pin "2") (pinfunction "2_2") (pintype "passive"))
      (node (ref "ICSP") (pin "6") (pinfunction "6_6") (pintype "passive"))
      (node (ref "JP1") (pin "CTS") (pinfunction "5_CTS") (pintype "passive"))
      (node (ref "JP1") (pin "GND") (pinfunction "6_GND") (pintype "passive"))
      (node (ref "PWLED") (pin "C") (pinfunction "C_C") (pintype "passive"))
      (node (ref "PWR") (pin "1") (pinfunction "1_1") (pintype "passive"))
      (node (ref "R17") (pin "1") (pinfunction "1_1") (pintype "passive"))
      (node (ref "R2") (pin "1") (pinfunction "1_1") (pintype "passive"))
      (node (ref "R3") (pin "1") (pinfunction "1_1") (pintype "passive"))
      (node (ref "R5") (pin "1") (pinfunction "1_1") (pintype "passive"))
      (node (ref "R7") (pin "1") (pinfunction "1_1") (pintype "passive"))
      (node (ref "REG18") (pin "2") (pinfunction "GND_2") (pintype "input"))
      (node (ref "REG33") (pin "2") (pinfunction "GND_2") (pintype "input"))
      (node (ref "REG5") (pin "2") (pinfunction "GND_2") (pintype "input"))
      (node (ref "R_EXT") (pin "P$1") (pinfunction "1_P$1") (pintype "passive"))
      (node (ref "S1") (pin "1") (pinfunction "1_1") (pintype "passive"))
      (node (ref "S1") (pin "2") (pinfunction "2_2") (pintype "passive"))
      (node (ref "SPKR") (pin "1") (pinfunction "1_1") (pintype "passive"))
      (node (ref "START") (pin "2") (pinfunction "2_2") (pintype "passive"))
      (node (ref "TR") (pin "1") (pinfunction "A_1") (pintype "passive"))
      (node (ref "U4") (pin "21") (pinfunction "GND_21") (pintype "bidirectional"))
      (node (ref "U4") (pin "3") (pinfunction "GND_3") (pintype "bidirectional"))
      (node (ref "U4") (pin "5") (pinfunction "AGND_5") (pintype "bidirectional"))
      (node (ref "U5") (pin "16") (pinfunction "DGND2_16") (pintype "bidirectional"))
      (node (ref "U5") (pin "20") (pinfunction "DGND3_20") (pintype "bidirectional"))
      (node (ref "U5") (pin "21") (pinfunction "DGND4_21") (pintype "bidirectional"))
      (node (ref "U5") (pin "22") (pinfunction "DGND5_22") (pintype "bidirectional"))
      (node (ref "U5") (pin "35") (pinfunction "DGND6_35") (pintype "bidirectional"))
      (node (ref "U5") (pin "37") (pinfunction "AGND1_37") (pintype "bidirectional"))
      (node (ref "U5") (pin "4") (pinfunction "DGND1_4") (pintype "bidirectional"))
      (node (ref "U5") (pin "40") (pinfunction "AGND2_40") (pintype "bidirectional"))
      (node (ref "U5") (pin "41") (pinfunction "AGND3_41") (pintype "bidirectional"))
      (node (ref "U5") (pin "47") (pinfunction "AGND4_47") (pintype "bidirectional"))
      (node (ref "U6") (pin "1") (pinfunction "GND_1") (pintype "power_in"))
      (node (ref "U6") (pin "21") (pinfunction "*OE_21") (pintype "output"))
      (node (ref "Y2") (pin "2") (pinfunction "2_2") (pintype "passive"))
    )
    (net (code "41") (name "Net-(AMP-+IN)") (class "Default")
      (node (ref "AMP") (pin "3") (pinfunction "+IN_3") (pintype "input"))
      (node (ref "C8") (pin "1") (pinfunction "1_1") (pintype "passive"))
    )
    (net (code "42") (name "Net-(AMP-GAIN-Pad1)") (class "Default")
      (node (ref "AMP") (pin "1") (pinfunction "GAIN_1") (pintype "passive"))
      (node (ref "C11") (pin "1") (pinfunction "1_1") (pintype "passive"))
    )
    (net (code "43") (name "Net-(AMP-GAIN-Pad8)") (class "Default")
      (node (ref "AMP") (pin "8") (pinfunction "GAIN_8") (pintype "passive"))
      (node (ref "C11") (pin "2") (pinfunction "2_2") (pintype "passive"))
    )
    (net (code "44") (name "Net-(AMP-OUT)") (class "Default")
      (node (ref "AMP") (pin "5") (pinfunction "OUT_5") (pintype "output"))
      (node (ref "C10") (pin "2") (pinfunction "2_2") (pintype "passive"))
      (node (ref "R22") (pin "2") (pinfunction "2_2") (pintype "passive"))
    )
    (net (code "45") (name "Net-(C7-Pad2)") (class "Default")
      (node (ref "C7") (pin "2") (pinfunction "2_2") (pintype "passive"))
      (node (ref "R21") (pin "1") (pinfunction "1_1") (pintype "passive"))
    )
    (net (code "46") (name "Net-(C9-Pad2)") (class "Default")
      (node (ref "C9") (pin "2") (pinfunction "2_2") (pintype "passive"))
      (node (ref "R22") (pin "1") (pinfunction "1_1") (pintype "passive"))
    )
    (net (code "47") (name "Net-(C10-Pad1)") (class "Default")
      (node (ref "C10") (pin "1") (pinfunction "1_1") (pintype "passive"))
      (node (ref "R23") (pin "2") (pinfunction "2_2") (pintype "passive"))
    )
    (net (code "48") (name "Net-(PWLED-PadA)") (class "Default")
      (node (ref "PWLED") (pin "A") (pinfunction "A_A") (pintype "passive"))
      (node (ref "R12") (pin "1") (pinfunction "1_1") (pintype "passive"))
    )
    (net (code "49") (name "Net-(R23-Pad1)") (class "Default")
      (node (ref "R23") (pin "1") (pinfunction "1_1") (pintype "passive"))
      (node (ref "SPKR") (pin "2") (pinfunction "2_2") (pintype "passive"))
    )
    (net (code "50") (name "Net-(REG33-BP)") (class "Default")
      (node (ref "33CBYP") (pin "1") (pinfunction "1_1") (pintype "passive"))
      (node (ref "REG33") (pin "4") (pinfunction "BP_4") (pintype "input"))
    )
    (net (code "51") (name "Net-(REG33-EN)") (class "Default")
      (node (ref "C3") (pin "1") (pinfunction "1_1") (pintype "passive"))
      (node (ref "R12") (pin "2") (pinfunction "2_2") (pintype "passive"))
      (node (ref "REG33") (pin "1") (pinfunction "IN_1") (pintype "input"))
      (node (ref "REG33") (pin "3") (pinfunction "EN_3") (pintype "input"))
      (node (ref "REG5") (pin "1") (pinfunction "IN_1") (pintype "input"))
      (node (ref "REG5") (pin "3") (pinfunction "EN_3") (pintype "input"))
      (node (ref "S4") (pin "3") (pinfunction "S_3") (pintype "passive"))
    )
    (net (code "52") (name "Net-(S4-P)") (class "Default")
      (node (ref "PWR") (pin "2") (pinfunction "2_2") (pintype "passive"))
      (node (ref "S4") (pin "2") (pinfunction "P_2") (pintype "passive"))
    )
    (net (code "53") (name "Net-(TR-E)") (class "Default")
      (node (ref "R11") (pin "1") (pinfunction "1_1") (pintype "passive"))
      (node (ref "TR") (pin "3") (pinfunction "E_3") (pintype "passive"))
    )
    (net (code "54") (name "Net-(TR-S)") (class "Default")
      (node (ref "C8") (pin "2") (pinfunction "2_2") (pintype "passive"))
      (node (ref "TR") (pin "2") (pinfunction "S_2") (pintype "passive"))
    )
    (net (code "55") (name "Net-(U4-AREF)") (class "Default")
      (node (ref "C2") (pin "2") (pinfunction "2_2") (pintype "passive"))
      (node (ref "U4") (pin "20") (pinfunction "AREF_20") (pintype "bidirectional"))
    )
    (net (code "56") (name "Net-(U4-PB0(ICP))") (class "Default")
      (node (ref "R14") (pin "2") (pinfunction "2_2") (pintype "passive"))
      (node (ref "U4") (pin "12") (pinfunction "PB0(ICP)_12") (pintype "bidirectional"))
    )
    (net (code "57") (name "Net-(U4-PB6(XTAL1{slash}TOSC1))") (class "Default")
      (node (ref "U4") (pin "7") (pinfunction "PB6(XTAL1/TOSC1)_7") (pintype "bidirectional"))
      (node (ref "Y2") (pin "1") (pinfunction "1_1") (pintype "passive"))
    )
    (net (code "58") (name "Net-(U4-PB7(XTAL2{slash}TOSC2))") (class "Default")
      (node (ref "U4") (pin "8") (pinfunction "PB7(XTAL2/TOSC2)_8") (pintype "bidirectional"))
      (node (ref "Y2") (pin "3") (pinfunction "3_3") (pintype "passive"))
    )
    (net (code "59") (name "Net-(U4-PD7(AIN1))") (class "Default")
      (node (ref "R1") (pin "2") (pinfunction "2_2") (pintype "passive"))
      (node (ref "U4") (pin "11") (pinfunction "PD7(AIN1)_11") (pintype "bidirectional"))
    )
    (net (code "60") (name "Net-(U5-GPIO2{slash}DCLK)") (class "Default")
      (node (ref "R5") (pin "2") (pinfunction "2_2") (pintype "passive"))
      (node (ref "U5") (pin "10") (pinfunction "GPIO3/SDATA_10") (pintype "bidirectional"))
      (node (ref "U5") (pin "11") (pinfunction "GPIO6_11") (pintype "bidirectional"))
      (node (ref "U5") (pin "12") (pinfunction "GPIO7_12") (pintype "bidirectional"))
      (node (ref "U5") (pin "9") (pinfunction "GPIO2/DCLK_9") (pintype "bidirectional"))
    )
    (net (code "61") (name "Net-(U5-GPIO4{slash}I2S_LROUT)") (class "Default")
      (node (ref "R2") (pin "2") (pinfunction "2_2") (pintype "passive"))
      (node (ref "U5") (pin "36") (pinfunction "GPIO4/I2S_LROUT_36") (pintype "bidirectional"))
    )
    (net (code "62") (name "Net-(U5-GPIO5{slash}I2C_MCLK)") (class "Default")
      (node (ref "R3") (pin "2") (pinfunction "2_2") (pintype "passive"))
      (node (ref "U5") (pin "25") (pinfunction "GPIO5/I2C_MCLK_25") (pintype "bidirectional"))
    )
    (net (code "63") (name "Net-(U5-RCAP)") (class "Default")
      (node (ref "C6") (pin "1") (pinfunction "1_1") (pintype "passive"))
      (node (ref "U5") (pin "44") (pinfunction "RCAP_44") (pintype "bidirectional"))
    )
    (net (code "64") (name "Net-(U5-XTAL1{slash}MCLK)") (class "Default")
      (node (ref "C4") (pin "2") (pinfunction "2_2") (pintype "passive"))
      (node (ref "R8") (pin "2") (pinfunction "2_2") (pintype "passive"))
      (node (ref "U5") (pin "18") (pinfunction "XTAL1/MCLK_18") (pintype "bidirectional"))
      (node (ref "Y1") (pin "3") (pinfunction "2_3") (pintype "passive"))
    )
    (net (code "65") (name "Net-(U5-XTAL2)") (class "Default")
      (node (ref "C5") (pin "2") (pinfunction "2_2") (pintype "passive"))
      (node (ref "R8") (pin "1") (pinfunction "1_1") (pintype "passive"))
      (node (ref "U5") (pin "17") (pinfunction "XTAL2_17") (pintype "bidirectional"))
      (node (ref "Y1") (pin "1") (pinfunction "1_1") (pintype "passive"))
    )
    (net (code "66") (name "unconnected-(AMP-BYPASS-Pad7)") (class "Default")
      (node (ref "AMP") (pin "7") (pinfunction "BYPASS_7") (pintype "passive"))
    )
    (net (code "67") (name "unconnected-(REG5-BP-Pad4)") (class "Default")
      (node (ref "REG5") (pin "4") (pinfunction "BP_4") (pintype "input"))
    )
    (net (code "68") (name "unconnected-(REG18-BP-Pad4)") (class "Default")
      (node (ref "REG18") (pin "4") (pinfunction "BP_4") (pintype "input"))
    )
    (net (code "69") (name "unconnected-(S4-O-Pad1)") (class "Default")
      (node (ref "S4") (pin "1") (pinfunction "O_1") (pintype "passive"))
    )
    (net (code "70") (name "unconnected-(U4-ADC6-Pad19)") (class "Default")
      (node (ref "U4") (pin "19") (pinfunction "ADC6_19") (pintype "bidirectional"))
    )
    (net (code "71") (name "unconnected-(U4-ADC7-Pad22)") (class "Default")
      (node (ref "U4") (pin "22") (pinfunction "ADC7_22") (pintype "bidirectional"))
    )
    (net (code "72") (name "unconnected-(U4-AVCC-Pad18)") (class "Default")
      (node (ref "U4") (pin "18") (pinfunction "AVCC_18") (pintype "bidirectional"))
    )
    (net (code "73") (name "unconnected-(U4-PC1(ADC1)-Pad24)") (class "Default")
      (node (ref "U4") (pin "24") (pinfunction "PC1(ADC1)_24") (pintype "bidirectional"))
    )
    (net (code "74") (name "unconnected-(U4-PC2(ADC2)-Pad25)") (class "Default")
      (node (ref "U4") (pin "25") (pinfunction "PC2(ADC2)_25") (pintype "bidirectional"))
    )
    (net (code "75") (name "unconnected-(U4-PC3(ADC3)-Pad26)") (class "Default")
      (node (ref "U4") (pin "26") (pinfunction "PC3(ADC3)_26") (pintype "bidirectional"))
    )
    (net (code "76") (name "unconnected-(U4-PC4(ADC4{slash}SDA)-Pad27)") (class "Default")
      (node (ref "U4") (pin "27") (pinfunction "PC4(ADC4/SDA)_27") (pintype "bidirectional"))
    )
    (net (code "77") (name "unconnected-(U4-PC5(ADC5{slash}SCL)-Pad28)") (class "Default")
      (node (ref "U4") (pin "28") (pinfunction "PC5(ADC5/SCL)_28") (pintype "bidirectional"))
    )
    (net (code "78") (name "unconnected-(U5-DREQ-Pad8)") (class "Default")
      (node (ref "U5") (pin "8") (pinfunction "DREQ_8") (pintype "bidirectional"))
    )
    (net (code "79") (name "unconnected-(U5-GBUF-Pad42)") (class "Default")
      (node (ref "U5") (pin "42") (pinfunction "GBUF_42") (pintype "bidirectional"))
    )
    (net (code "80") (name "unconnected-(U5-LINEIN-Pad48)") (class "Default")
      (node (ref "U5") (pin "48") (pinfunction "LINEIN_48") (pintype "bidirectional"))
    )
    (net (code "81") (name "unconnected-(U5-MICN-Pad2)") (class "Default")
      (node (ref "U5") (pin "2") (pinfunction "MICN_2") (pintype "bidirectional"))
    )
    (net (code "82") (name "unconnected-(U5-MICP-Pad1)") (class "Default")
      (node (ref "U5") (pin "1") (pinfunction "MICP_1") (pintype "bidirectional"))
    )
    (net (code "83") (name "unconnected-(U5-RIGHT-Pad39)") (class "Default")
      (node (ref "U5") (pin "39") (pinfunction "RIGHT_39") (pintype "bidirectional"))
    )
    (net (code "84") (name "unconnected-(U5-S0-Pad30)") (class "Default")
      (node (ref "U5") (pin "30") (pinfunction "S0_30") (pintype "bidirectional"))
    )
    (net (code "85") (name "unconnected-(U5-SCLK-Pad28)") (class "Default")
      (node (ref "U5") (pin "28") (pinfunction "SCLK_28") (pintype "bidirectional"))
    )
    (net (code "86") (name "unconnected-(U5-SI-Pad29)") (class "Default")
      (node (ref "U5") (pin "29") (pinfunction "SI_29") (pintype "bidirectional"))
    )
    (net (code "87") (name "unconnected-(U5-TX-Pad27)") (class "Default")
      (node (ref "U5") (pin "27") (pinfunction "TX_27") (pintype "bidirectional"))
    )
    (net (code "88") (name "unconnected-(U5-VCO-Pad15)") (class "Default")
      (node (ref "U5") (pin "15") (pinfunction "VCO_15") (pintype "bidirectional"))
    )
    (net (code "89") (name "unconnected-(U5-XCS-Pad23)") (class "Default")
      (node (ref "U5") (pin "23") (pinfunction "XCS_23") (pintype "bidirectional"))
    )
    (net (code "90") (name "unconnected-(U5-XDCS{slash}BSYNC-Pad13)") (class "Default")
      (node (ref "U5") (pin "13") (pinfunction "XDCS/BSYNC_13") (pintype "bidirectional"))
    )
    (net (code "91") (name "unconnected-(U6-SDO-Pad22)") (class "Default")
      (node (ref "U6") (pin "22") (pinfunction "SDO_22") (pintype "output"))
    )
  )
)
